# union.net
KiCad netlist of a schematic drawn in EAGLE
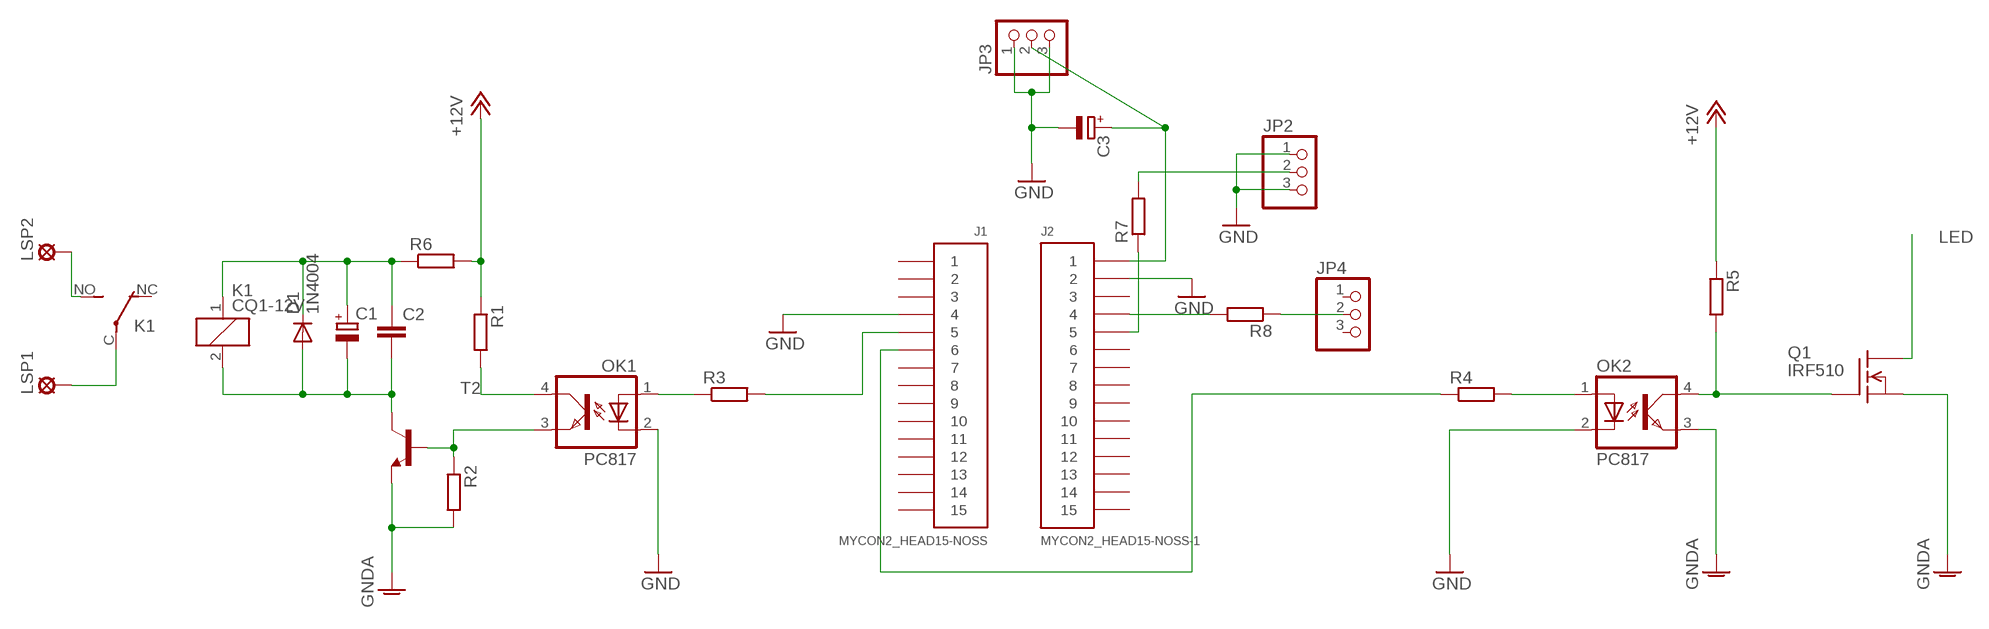
[diagram p0: schematic, sheet 1]

(export (version "E")
  (design (tool "Eeschema 10.0.6"))
  (components
    (comp (ref "C1")
      (value "CPOL-EUE3.5-8")
      (footprint "eagle-import:E3,5-8")
      (libsource (lib "eagle-import") (part "CPOL-EUE3.5-8"))
    )
    (comp (ref "C2")
      (value "C-EUC1206")
      (footprint "eagle-import:C1206")
      (libsource (lib "eagle-import") (part "C-EUC1206"))
    )
    (comp (ref "C3")
      (value "CPOL-EUE3.5-8")
      (footprint "eagle-import:E3,5-8")
      (libsource (lib "eagle-import") (part "CPOL-EUE3.5-8"))
    )
    (comp (ref "D1")
      (value "1N4004")
      (footprint "eagle-import:DO41-10")
      (libsource (lib "eagle-import") (part "1N4004"))
    )
    (comp (ref "J1")
      (value "MYCON2_HEAD15-NOSS")
      (footprint "eagle-import:MYCON2_HEAD15-NOSS")
      (libsource (lib "eagle-import") (part "MYCON2_HEAD15-NOSS"))
    )
    (comp (ref "J2")
      (value "MYCON2_HEAD15-NOSS-1")
      (footprint "eagle-import:MYCON2_HEAD15-NOSS-1")
      (libsource (lib "eagle-import") (part "MYCON2_HEAD15-NOSS-1"))
    )
    (comp (ref "JP2")
      (value "PINHD-1X3")
      (footprint "eagle-import:1X03")
      (libsource (lib "eagle-import") (part "PINHD-1X3"))
    )
    (comp (ref "JP3")
      (value "PINHD-1X3")
      (footprint "eagle-import:1X03")
      (libsource (lib "eagle-import") (part "PINHD-1X3"))
    )
    (comp (ref "JP4")
      (value "PINHD-1X3")
      (footprint "eagle-import:1X03")
      (libsource (lib "eagle-import") (part "PINHD-1X3"))
    )
    (comp (ref "K1")
      (value "CQ1-12V")
      (footprint "eagle-import:CQ1")
      (libsource (lib "eagle-import") (part "CQ1-12V"))
    )
    (comp (ref "LSP1")
      (value "LSP10")
      (footprint "eagle-import:LSP10")
      (libsource (lib "eagle-import") (part "LSP10"))
    )
    (comp (ref "LSP2")
      (value "LSP10")
      (footprint "eagle-import:LSP10")
      (libsource (lib "eagle-import") (part "LSP10"))
    )
    (comp (ref "OK1")
      (value "PC817")
      (footprint "eagle-import:DIL04")
      (fields (field (name "MPN") "PC817X4J000F"))
      (libsource (lib "eagle-import") (part "PC817"))
    )
    (comp (ref "OK2")
      (value "PC817")
      (footprint "eagle-import:DIL04")
      (fields (field (name "MPN") "PC817X4J000F"))
      (libsource (lib "eagle-import") (part "PC817"))
    )
    (comp (ref "Q1")
      (value "IRF510")
      (footprint "eagle-import:TO220")
      (libsource (lib "eagle-import") (part "IRF510"))
    )
    (comp (ref "R1")
      (value "R-EU_R1206")
      (footprint "eagle-import:R1206")
      (libsource (lib "eagle-import") (part "R-EU_R1206"))
    )
    (comp (ref "R2")
      (value "R-EU_R1206")
      (footprint "eagle-import:R1206")
      (libsource (lib "eagle-import") (part "R-EU_R1206"))
    )
    (comp (ref "R3")
      (value "R-EU_R1206")
      (footprint "eagle-import:R1206")
      (libsource (lib "eagle-import") (part "R-EU_R1206"))
    )
    (comp (ref "R4")
      (value "R-EU_R1206")
      (footprint "eagle-import:R1206")
      (libsource (lib "eagle-import") (part "R-EU_R1206"))
    )
    (comp (ref "R5")
      (value "R-EU_R1206")
      (footprint "eagle-import:R1206")
      (libsource (lib "eagle-import") (part "R-EU_R1206"))
    )
    (comp (ref "R6")
      (value "R-EU_0204/5")
      (footprint "eagle-import:0204_5")
      (libsource (lib "eagle-import") (part "resistor_R-EU_0204/5"))
    )
    (comp (ref "R7")
      (value "R-EU_R1206")
      (footprint "eagle-import:R1206")
      (libsource (lib "eagle-import") (part "R-EU_R1206"))
    )
    (comp (ref "R8")
      (value "R-EU_R1206")
      (footprint "eagle-import:R1206")
      (libsource (lib "eagle-import") (part "R-EU_R1206"))
    )
    (comp (ref "T2")
      (value "-NPN-TO92")
      (footprint "eagle-import:TO92")
      (libsource (lib "eagle-import") (part "-NPN-TO92"))
    )
  )
  (nets
    (net (code "1") (name "+12V") (class "Default")
      (node (ref "R1") (pin "1") (pinfunction "1_1") (pintype "passive"))
      (node (ref "R5") (pin "1") (pinfunction "1_1") (pintype "passive"))
      (node (ref "R6") (pin "2") (pinfunction "2_2") (pintype "passive"))
    )
    (net (code "2") (name "/LED") (class "Default")
      (node (ref "Q1") (pin "2") (pinfunction "D_2") (pintype "passive"))
    )
    (net (code "3") (name "GND") (class "Default")
      (node (ref "C3") (pin "-") (pinfunction "-_-") (pintype "passive"))
      (node (ref "J1") (pin "4") (pinfunction "4_4") (pintype "passive"))
      (node (ref "J2") (pin "2") (pinfunction "2_2") (pintype "passive"))
      (node (ref "JP2") (pin "1") (pinfunction "1_1") (pintype "passive"))
      (node (ref "JP2") (pin "3") (pinfunction "3_3") (pintype "passive"))
      (node (ref "JP3") (pin "1") (pinfunction "1_1") (pintype "passive"))
      (node (ref "JP3") (pin "3") (pinfunction "3_3") (pintype "passive"))
      (node (ref "OK1") (pin "2") (pinfunction "C_2") (pintype "passive"))
      (node (ref "OK2") (pin "2") (pinfunction "C_2") (pintype "passive"))
    )
    (net (code "4") (name "GNDA") (class "Default")
      (node (ref "OK2") (pin "3") (pinfunction "EMIT_3") (pintype "passive"))
      (node (ref "Q1") (pin "3") (pinfunction "S_3") (pintype "passive"))
      (node (ref "R2") (pin "2") (pinfunction "2_2") (pintype "passive"))
      (node (ref "T2") (pin "1") (pinfunction "E_1") (pintype "passive"))
    )
    (net (code "5") (name "Net-(C1-Pad+)") (class "Default")
      (node (ref "C1") (pin "+") (pinfunction "+_+") (pintype "passive"))
      (node (ref "C2") (pin "1") (pinfunction "1_1") (pintype "passive"))
      (node (ref "D1") (pin "C") (pinfunction "C_C") (pintype "passive"))
      (node (ref "K1") (pin "1") (pinfunction "1_1") (pintype "passive"))
      (node (ref "R6") (pin "1") (pinfunction "1_1") (pintype "passive"))
    )
    (net (code "6") (name "Net-(C3-Pad+)") (class "Default")
      (node (ref "C3") (pin "+") (pinfunction "+_+") (pintype "passive"))
      (node (ref "J2") (pin "1") (pinfunction "1_1") (pintype "passive"))
      (node (ref "JP3") (pin "2") (pinfunction "2_2") (pintype "passive"))
    )
    (net (code "7") (name "Net-(J1-Pad5)") (class "Default")
      (node (ref "J1") (pin "5") (pinfunction "5_5") (pintype "passive"))
      (node (ref "R3") (pin "2") (pinfunction "2_2") (pintype "passive"))
    )
    (net (code "8") (name "Net-(J1-Pad6)") (class "Default")
      (node (ref "J1") (pin "6") (pinfunction "6_6") (pintype "passive"))
      (node (ref "R4") (pin "1") (pinfunction "1_1") (pintype "passive"))
    )
    (net (code "9") (name "Net-(J2-Pad4)") (class "Default")
      (node (ref "J2") (pin "4") (pinfunction "4_4") (pintype "passive"))
      (node (ref "R8") (pin "2") (pinfunction "2_2") (pintype "passive"))
    )
    (net (code "10") (name "Net-(J2-Pad5)") (class "Default")
      (node (ref "J2") (pin "5") (pinfunction "5_5") (pintype "passive"))
      (node (ref "R7") (pin "1") (pinfunction "1_1") (pintype "passive"))
    )
    (net (code "11") (name "Net-(JP2-Pad2)") (class "Default")
      (node (ref "JP2") (pin "2") (pinfunction "2_2") (pintype "passive"))
      (node (ref "R7") (pin "2") (pinfunction "2_2") (pintype "passive"))
    )
    (net (code "12") (name "Net-(JP4-Pad2)") (class "Default")
      (node (ref "JP4") (pin "2") (pinfunction "2_2") (pintype "passive"))
      (node (ref "R8") (pin "1") (pinfunction "1_1") (pintype "passive"))
    )
    (net (code "13") (name "Net-(K1B-P)") (class "Default")
      (node (ref "K1") (pin "C") (pinfunction "P_C") (pintype "passive"))
      (node (ref "LSP1") (pin "MP") (pinfunction "MP_MP") (pintype "passive"))
    )
    (net (code "14") (name "Net-(K1B-S)") (class "Default")
      (node (ref "K1") (pin "NO") (pinfunction "S_NO") (pintype "passive"))
      (node (ref "LSP2") (pin "MP") (pinfunction "MP_MP") (pintype "passive"))
    )
    (net (code "15") (name "Net-(OK1-A)") (class "Default")
      (node (ref "OK1") (pin "1") (pinfunction "A_1") (pintype "passive"))
      (node (ref "R3") (pin "1") (pinfunction "1_1") (pintype "passive"))
    )
    (net (code "16") (name "Net-(OK1-COL)") (class "Default")
      (node (ref "OK1") (pin "4") (pinfunction "COL_4") (pintype "passive"))
      (node (ref "R1") (pin "2") (pinfunction "2_2") (pintype "passive"))
    )
    (net (code "17") (name "Net-(OK1-EMIT)") (class "Default")
      (node (ref "OK1") (pin "3") (pinfunction "EMIT_3") (pintype "passive"))
      (node (ref "R2") (pin "1") (pinfunction "1_1") (pintype "passive"))
      (node (ref "T2") (pin "2") (pinfunction "B_2") (pintype "passive"))
    )
    (net (code "18") (name "Net-(OK2-A)") (class "Default")
      (node (ref "OK2") (pin "1") (pinfunction "A_1") (pintype "passive"))
      (node (ref "R4") (pin "2") (pinfunction "2_2") (pintype "passive"))
    )
    (net (code "19") (name "Net-(OK2-COL)") (class "Default")
      (node (ref "OK2") (pin "4") (pinfunction "COL_4") (pintype "passive"))
      (node (ref "Q1") (pin "1") (pinfunction "G_1") (pintype "passive"))
      (node (ref "R5") (pin "2") (pinfunction "2_2") (pintype "passive"))
    )
    (net (code "20") (name "Net-(T2-C)") (class "Default")
      (node (ref "C1") (pin "-") (pinfunction "-_-") (pintype "passive"))
      (node (ref "C2") (pin "2") (pinfunction "2_2") (pintype "passive"))
      (node (ref "D1") (pin "A") (pinfunction "A_A") (pintype "passive"))
      (node (ref "K1") (pin "2") (pinfunction "2_2") (pintype "passive"))
      (node (ref "T2") (pin "3") (pinfunction "C_3") (pintype "passive"))
    )
    (net (code "21") (name "unconnected-(J1-Pad1)") (class "Default")
      (node (ref "J1") (pin "1") (pinfunction "1_1") (pintype "passive"))
    )
    (net (code "22") (name "unconnected-(J1-Pad2)") (class "Default")
      (node (ref "J1") (pin "2") (pinfunction "2_2") (pintype "passive"))
    )
    (net (code "23") (name "unconnected-(J1-Pad3)") (class "Default")
      (node (ref "J1") (pin "3") (pinfunction "3_3") (pintype "passive"))
    )
    (net (code "24") (name "unconnected-(J1-Pad7)") (class "Default")
      (node (ref "J1") (pin "7") (pinfunction "7_7") (pintype "passive"))
    )
    (net (code "25") (name "unconnected-(J1-Pad8)") (class "Default")
      (node (ref "J1") (pin "8") (pinfunction "8_8") (pintype "passive"))
    )
    (net (code "26") (name "unconnected-(J1-Pad9)") (class "Default")
      (node (ref "J1") (pin "9") (pinfunction "9_9") (pintype "passive"))
    )
    (net (code "27") (name "unconnected-(J1-Pad10)") (class "Default")
      (node (ref "J1") (pin "10") (pinfunction "10_10") (pintype "passive"))
    )
    (net (code "28") (name "unconnected-(J1-Pad11)") (class "Default")
      (node (ref "J1") (pin "11") (pinfunction "11_11") (pintype "passive"))
    )
    (net (code "29") (name "unconnected-(J1-Pad12)") (class "Default")
      (node (ref "J1") (pin "12") (pinfunction "12_12") (pintype "passive"))
    )
    (net (code "30") (name "unconnected-(J1-Pad13)") (class "Default")
      (node (ref "J1") (pin "13") (pinfunction "13_13") (pintype "passive"))
    )
    (net (code "31") (name "unconnected-(J1-Pad14)") (class "Default")
      (node (ref "J1") (pin "14") (pinfunction "14_14") (pintype "passive"))
    )
    (net (code "32") (name "unconnected-(J1-Pad15)") (class "Default")
      (node (ref "J1") (pin "15") (pinfunction "15_15") (pintype "passive"))
    )
    (net (code "33") (name "unconnected-(J2-Pad3)") (class "Default")
      (node (ref "J2") (pin "3") (pinfunction "3_3") (pintype "passive"))
    )
    (net (code "34") (name "unconnected-(J2-Pad6)") (class "Default")
      (node (ref "J2") (pin "6") (pinfunction "6_6") (pintype "passive"))
    )
    (net (code "35") (name "unconnected-(J2-Pad7)") (class "Default")
      (node (ref "J2") (pin "7") (pinfunction "7_7") (pintype "passive"))
    )
    (net (code "36") (name "unconnected-(J2-Pad8)") (class "Default")
      (node (ref "J2") (pin "8") (pinfunction "8_8") (pintype "passive"))
    )
    (net (code "37") (name "unconnected-(J2-Pad9)") (class "Default")
      (node (ref "J2") (pin "9") (pinfunction "9_9") (pintype "passive"))
    )
    (net (code "38") (name "unconnected-(J2-Pad10)") (class "Default")
      (node (ref "J2") (pin "10") (pinfunction "10_10") (pintype "passive"))
    )
    (net (code "39") (name "unconnected-(J2-Pad11)") (class "Default")
      (node (ref "J2") (pin "11") (pinfunction "11_11") (pintype "passive"))
    )
    (net (code "40") (name "unconnected-(J2-Pad12)") (class "Default")
      (node (ref "J2") (pin "12") (pinfunction "12_12") (pintype "passive"))
    )
    (net (code "41") (name "unconnected-(J2-Pad13)") (class "Default")
      (node (ref "J2") (pin "13") (pinfunction "13_13") (pintype "passive"))
    )
    (net (code "42") (name "unconnected-(J2-Pad14)") (class "Default")
      (node (ref "J2") (pin "14") (pinfunction "14_14") (pintype "passive"))
    )
    (net (code "43") (name "unconnected-(J2-Pad15)") (class "Default")
      (node (ref "J2") (pin "15") (pinfunction "15_15") (pintype "passive"))
    )
    (net (code "44") (name "unconnected-(JP4-Pad1)") (class "Default")
      (node (ref "JP4") (pin "1") (pinfunction "1_1") (pintype "passive"))
    )
    (net (code "45") (name "unconnected-(JP4-Pad3)") (class "Default")
      (node (ref "JP4") (pin "3") (pinfunction "3_3") (pintype "passive"))
    )
    (net (code "46") (name "unconnected-(K1B-O-PadNC)") (class "Default")
      (node (ref "K1") (pin "NC") (pinfunction "O_NC") (pintype "passive"))
    )
  )
)
